# Accumulator_Register.net
KiCad netlist of a schematic drawn in Altium Designer
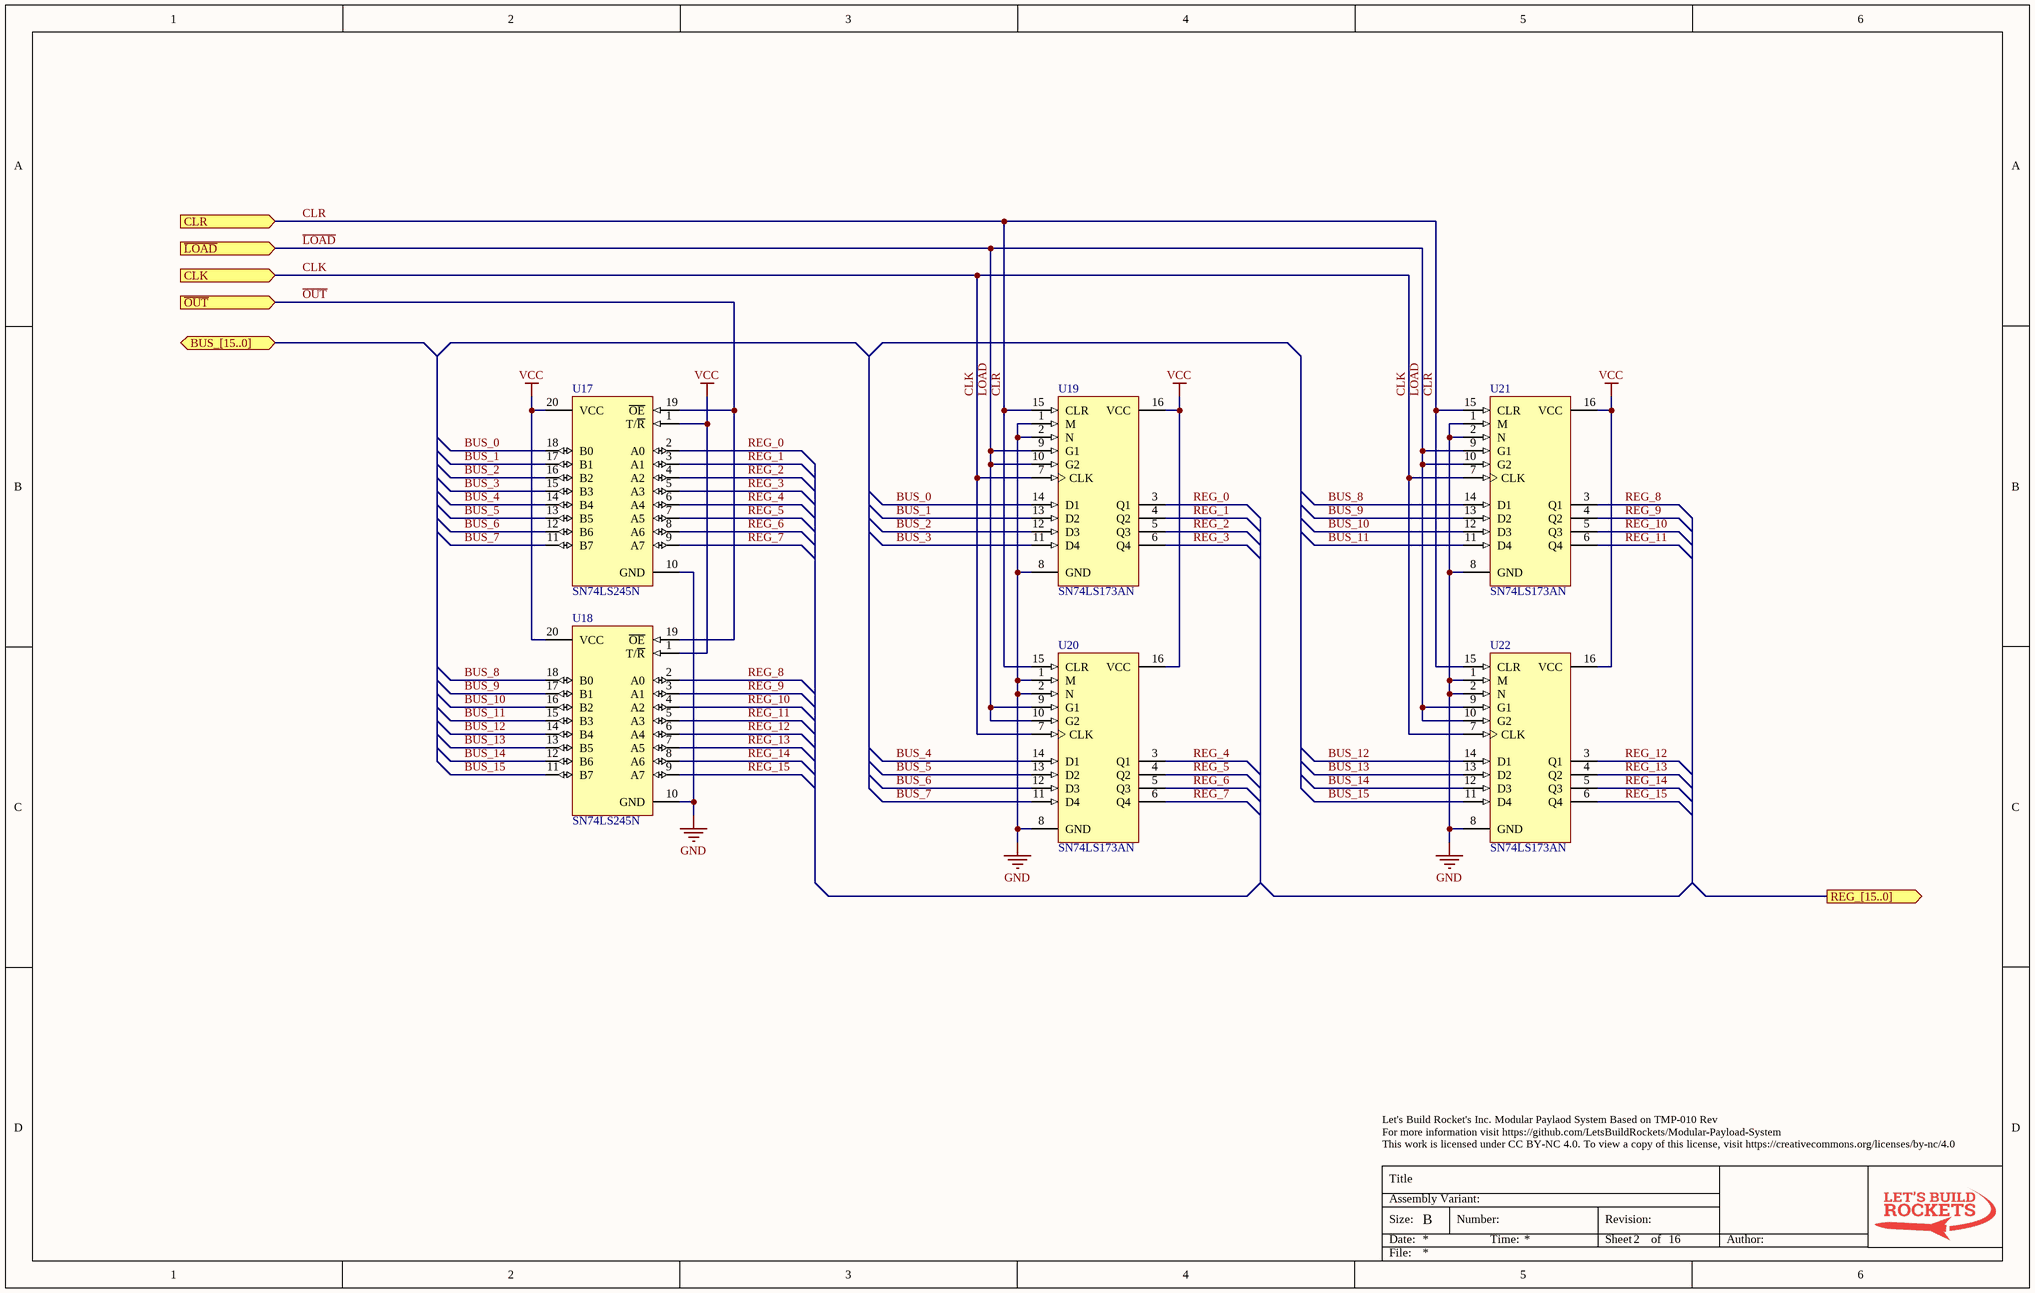
[diagram p0: Accumulator_Register.SchDoc]

(export (version "E")
  (design (tool "Eeschema 10.0.6"))
  (components
    (comp (ref "U17")
      (value "SN74LS245N")
      (footprint "N020")
      (description "Octal Bus Transceiver with 3-State Outputs")
      (fields (field (name "PUBLISHER") "Altium Limited"))
      (libsource (lib "TI Interface 8-Bit Line Transceiver") (part "SN74LS245N"))
    )
    (comp (ref "U18")
      (value "SN74LS245N")
      (footprint "N020")
      (description "Octal Bus Transceiver with 3-State Outputs")
      (fields (field (name "PUBLISHER") "Altium Limited"))
      (libsource (lib "TI Interface 8-Bit Line Transceiver") (part "SN74LS245N"))
    )
    (comp (ref "U19")
      (value "SN74LS173AN")
      (footprint "N016D")
      (description "4-Bit D-Type Register with 3-State Outputs")
      (fields (field (name "PUBLISHER") "Altium Limited"))
      (libsource (lib "TI Logic Flip-Flop") (part "SN74LS173AN"))
    )
    (comp (ref "U20")
      (value "SN74LS173AN")
      (footprint "N016D")
      (description "4-Bit D-Type Register with 3-State Outputs")
      (fields (field (name "PUBLISHER") "Altium Limited"))
      (libsource (lib "TI Logic Flip-Flop") (part "SN74LS173AN"))
    )
    (comp (ref "U21")
      (value "SN74LS173AN")
      (footprint "N016D")
      (description "4-Bit D-Type Register with 3-State Outputs")
      (fields (field (name "PUBLISHER") "Altium Limited"))
      (libsource (lib "TI Logic Flip-Flop") (part "SN74LS173AN"))
    )
    (comp (ref "U22")
      (value "SN74LS173AN")
      (footprint "N016D")
      (description "4-Bit D-Type Register with 3-State Outputs")
      (fields (field (name "PUBLISHER") "Altium Limited"))
      (libsource (lib "TI Logic Flip-Flop") (part "SN74LS173AN"))
    )
  )
  (nets
    (net (code "1") (name "/BUS_0") (class "Default")
      (node (ref "U17") (pin "18") (pinfunction "B0_18") (pintype "bidirectional"))
      (node (ref "U19") (pin "14") (pinfunction "D1_14") (pintype "input"))
    )
    (net (code "2") (name "/BUS_1") (class "Default")
      (node (ref "U17") (pin "17") (pinfunction "B1_17") (pintype "bidirectional"))
      (node (ref "U19") (pin "13") (pinfunction "D2_13") (pintype "input"))
    )
    (net (code "3") (name "/BUS_2") (class "Default")
      (node (ref "U17") (pin "16") (pinfunction "B2_16") (pintype "bidirectional"))
      (node (ref "U19") (pin "12") (pinfunction "D3_12") (pintype "input"))
    )
    (net (code "4") (name "/BUS_3") (class "Default")
      (node (ref "U17") (pin "15") (pinfunction "B3_15") (pintype "bidirectional"))
      (node (ref "U19") (pin "11") (pinfunction "D4_11") (pintype "input"))
    )
    (net (code "5") (name "/BUS_4") (class "Default")
      (node (ref "U17") (pin "14") (pinfunction "B4_14") (pintype "bidirectional"))
      (node (ref "U20") (pin "14") (pinfunction "D1_14") (pintype "input"))
    )
    (net (code "6") (name "/BUS_5") (class "Default")
      (node (ref "U17") (pin "13") (pinfunction "B5_13") (pintype "bidirectional"))
      (node (ref "U20") (pin "13") (pinfunction "D2_13") (pintype "input"))
    )
    (net (code "7") (name "/BUS_6") (class "Default")
      (node (ref "U17") (pin "12") (pinfunction "B6_12") (pintype "bidirectional"))
      (node (ref "U20") (pin "12") (pinfunction "D3_12") (pintype "input"))
    )
    (net (code "8") (name "/BUS_7") (class "Default")
      (node (ref "U17") (pin "11") (pinfunction "B7_11") (pintype "bidirectional"))
      (node (ref "U20") (pin "11") (pinfunction "D4_11") (pintype "input"))
    )
    (net (code "9") (name "/BUS_8") (class "Default")
      (node (ref "U18") (pin "18") (pinfunction "B0_18") (pintype "bidirectional"))
      (node (ref "U21") (pin "14") (pinfunction "D1_14") (pintype "input"))
    )
    (net (code "10") (name "/BUS_9") (class "Default")
      (node (ref "U18") (pin "17") (pinfunction "B1_17") (pintype "bidirectional"))
      (node (ref "U21") (pin "13") (pinfunction "D2_13") (pintype "input"))
    )
    (net (code "11") (name "/BUS_10") (class "Default")
      (node (ref "U18") (pin "16") (pinfunction "B2_16") (pintype "bidirectional"))
      (node (ref "U21") (pin "12") (pinfunction "D3_12") (pintype "input"))
    )
    (net (code "12") (name "/BUS_11") (class "Default")
      (node (ref "U18") (pin "15") (pinfunction "B3_15") (pintype "bidirectional"))
      (node (ref "U21") (pin "11") (pinfunction "D4_11") (pintype "input"))
    )
    (net (code "13") (name "/BUS_12") (class "Default")
      (node (ref "U18") (pin "14") (pinfunction "B4_14") (pintype "bidirectional"))
      (node (ref "U22") (pin "14") (pinfunction "D1_14") (pintype "input"))
    )
    (net (code "14") (name "/BUS_13") (class "Default")
      (node (ref "U18") (pin "13") (pinfunction "B5_13") (pintype "bidirectional"))
      (node (ref "U22") (pin "13") (pinfunction "D2_13") (pintype "input"))
    )
    (net (code "15") (name "/BUS_14") (class "Default")
      (node (ref "U18") (pin "12") (pinfunction "B6_12") (pintype "bidirectional"))
      (node (ref "U22") (pin "12") (pinfunction "D3_12") (pintype "input"))
    )
    (net (code "16") (name "/BUS_15") (class "Default")
      (node (ref "U18") (pin "11") (pinfunction "B7_11") (pintype "bidirectional"))
      (node (ref "U22") (pin "11") (pinfunction "D4_11") (pintype "input"))
    )
    (net (code "18") (name "/CLK") (class "Default")
      (node (ref "U19") (pin "7") (pinfunction "CLK_7") (pintype "input"))
      (node (ref "U20") (pin "7") (pinfunction "CLK_7") (pintype "input"))
      (node (ref "U21") (pin "7") (pinfunction "CLK_7") (pintype "input"))
      (node (ref "U22") (pin "7") (pinfunction "CLK_7") (pintype "input"))
    )
    (net (code "19") (name "/CLR") (class "Default")
      (node (ref "U19") (pin "15") (pinfunction "CLR_15") (pintype "input"))
      (node (ref "U20") (pin "15") (pinfunction "CLR_15") (pintype "input"))
      (node (ref "U21") (pin "15") (pinfunction "CLR_15") (pintype "input"))
      (node (ref "U22") (pin "15") (pinfunction "CLR_15") (pintype "input"))
    )
    (net (code "20") (name "/REG_0") (class "Default")
      (node (ref "U17") (pin "2") (pinfunction "A0_2") (pintype "bidirectional"))
      (node (ref "U19") (pin "3") (pinfunction "Q1_3") (pintype "tri_state"))
    )
    (net (code "21") (name "/REG_1") (class "Default")
      (node (ref "U17") (pin "3") (pinfunction "A1_3") (pintype "bidirectional"))
      (node (ref "U19") (pin "4") (pinfunction "Q2_4") (pintype "tri_state"))
    )
    (net (code "22") (name "/REG_2") (class "Default")
      (node (ref "U17") (pin "4") (pinfunction "A2_4") (pintype "bidirectional"))
      (node (ref "U19") (pin "5") (pinfunction "Q3_5") (pintype "tri_state"))
    )
    (net (code "23") (name "/REG_3") (class "Default")
      (node (ref "U17") (pin "5") (pinfunction "A3_5") (pintype "bidirectional"))
      (node (ref "U19") (pin "6") (pinfunction "Q4_6") (pintype "tri_state"))
    )
    (net (code "24") (name "/REG_4") (class "Default")
      (node (ref "U17") (pin "6") (pinfunction "A4_6") (pintype "bidirectional"))
      (node (ref "U20") (pin "3") (pinfunction "Q1_3") (pintype "tri_state"))
    )
    (net (code "25") (name "/REG_5") (class "Default")
      (node (ref "U17") (pin "7") (pinfunction "A5_7") (pintype "bidirectional"))
      (node (ref "U20") (pin "4") (pinfunction "Q2_4") (pintype "tri_state"))
    )
    (net (code "26") (name "/REG_6") (class "Default")
      (node (ref "U17") (pin "8") (pinfunction "A6_8") (pintype "bidirectional"))
      (node (ref "U20") (pin "5") (pinfunction "Q3_5") (pintype "tri_state"))
    )
    (net (code "27") (name "/REG_7") (class "Default")
      (node (ref "U17") (pin "9") (pinfunction "A7_9") (pintype "bidirectional"))
      (node (ref "U20") (pin "6") (pinfunction "Q4_6") (pintype "tri_state"))
    )
    (net (code "28") (name "/REG_8") (class "Default")
      (node (ref "U18") (pin "2") (pinfunction "A0_2") (pintype "bidirectional"))
      (node (ref "U21") (pin "3") (pinfunction "Q1_3") (pintype "tri_state"))
    )
    (net (code "29") (name "/REG_9") (class "Default")
      (node (ref "U18") (pin "3") (pinfunction "A1_3") (pintype "bidirectional"))
      (node (ref "U21") (pin "4") (pinfunction "Q2_4") (pintype "tri_state"))
    )
    (net (code "30") (name "/REG_10") (class "Default")
      (node (ref "U18") (pin "4") (pinfunction "A2_4") (pintype "bidirectional"))
      (node (ref "U21") (pin "5") (pinfunction "Q3_5") (pintype "tri_state"))
    )
    (net (code "31") (name "/REG_11") (class "Default")
      (node (ref "U18") (pin "5") (pinfunction "A3_5") (pintype "bidirectional"))
      (node (ref "U21") (pin "6") (pinfunction "Q4_6") (pintype "tri_state"))
    )
    (net (code "32") (name "/REG_12") (class "Default")
      (node (ref "U18") (pin "6") (pinfunction "A4_6") (pintype "bidirectional"))
      (node (ref "U22") (pin "3") (pinfunction "Q1_3") (pintype "tri_state"))
    )
    (net (code "33") (name "/REG_13") (class "Default")
      (node (ref "U18") (pin "7") (pinfunction "A5_7") (pintype "bidirectional"))
      (node (ref "U22") (pin "4") (pinfunction "Q2_4") (pintype "tri_state"))
    )
    (net (code "34") (name "/REG_14") (class "Default")
      (node (ref "U18") (pin "8") (pinfunction "A6_8") (pintype "bidirectional"))
      (node (ref "U22") (pin "5") (pinfunction "Q3_5") (pintype "tri_state"))
    )
    (net (code "35") (name "/REG_15") (class "Default")
      (node (ref "U18") (pin "9") (pinfunction "A7_9") (pintype "bidirectional"))
      (node (ref "U22") (pin "6") (pinfunction "Q4_6") (pintype "tri_state"))
    )
    (net (code "37") (name "/~{LOAD}") (class "Default")
      (node (ref "U19") (pin "10") (pinfunction "G2_10") (pintype "input"))
      (node (ref "U19") (pin "9") (pinfunction "G1_9") (pintype "input"))
      (node (ref "U20") (pin "10") (pinfunction "G2_10") (pintype "input"))
      (node (ref "U20") (pin "9") (pinfunction "G1_9") (pintype "input"))
      (node (ref "U21") (pin "10") (pinfunction "G2_10") (pintype "input"))
      (node (ref "U21") (pin "9") (pinfunction "G1_9") (pintype "input"))
      (node (ref "U22") (pin "10") (pinfunction "G2_10") (pintype "input"))
      (node (ref "U22") (pin "9") (pinfunction "G1_9") (pintype "input"))
    )
    (net (code "38") (name "/~{OUT}") (class "Default")
      (node (ref "U17") (pin "19") (pinfunction "~{OE}_19") (pintype "input"))
      (node (ref "U18") (pin "19") (pinfunction "~{OE}_19") (pintype "input"))
    )
    (net (code "39") (name "GND") (class "Default")
      (node (ref "U17") (pin "10") (pinfunction "GND_10") (pintype "power_in"))
      (node (ref "U18") (pin "10") (pinfunction "GND_10") (pintype "power_in"))
      (node (ref "U19") (pin "1") (pinfunction "M_1") (pintype "input"))
      (node (ref "U19") (pin "2") (pinfunction "N_2") (pintype "input"))
      (node (ref "U19") (pin "8") (pinfunction "GND_8") (pintype "power_in"))
      (node (ref "U20") (pin "1") (pinfunction "M_1") (pintype "input"))
      (node (ref "U20") (pin "2") (pinfunction "N_2") (pintype "input"))
      (node (ref "U20") (pin "8") (pinfunction "GND_8") (pintype "power_in"))
      (node (ref "U21") (pin "1") (pinfunction "M_1") (pintype "input"))
      (node (ref "U21") (pin "2") (pinfunction "N_2") (pintype "input"))
      (node (ref "U21") (pin "8") (pinfunction "GND_8") (pintype "power_in"))
      (node (ref "U22") (pin "1") (pinfunction "M_1") (pintype "input"))
      (node (ref "U22") (pin "2") (pinfunction "N_2") (pintype "input"))
      (node (ref "U22") (pin "8") (pinfunction "GND_8") (pintype "power_in"))
    )
    (net (code "40") (name "VCC") (class "Default")
      (node (ref "U17") (pin "1") (pinfunction "T/~{R}_1") (pintype "input"))
      (node (ref "U17") (pin "20") (pinfunction "VCC_20") (pintype "power_in"))
      (node (ref "U18") (pin "1") (pinfunction "T/~{R}_1") (pintype "input"))
      (node (ref "U18") (pin "20") (pinfunction "VCC_20") (pintype "power_in"))
      (node (ref "U19") (pin "16") (pinfunction "VCC_16") (pintype "power_in"))
      (node (ref "U20") (pin "16") (pinfunction "VCC_16") (pintype "power_in"))
      (node (ref "U21") (pin "16") (pinfunction "VCC_16") (pintype "power_in"))
      (node (ref "U22") (pin "16") (pinfunction "VCC_16") (pintype "power_in"))
    )
  )
)
